# EIB_1xA79026-001_small_pins_v1_2_0_30mm.net
KiCad netlist of a schematic drawn in EAGLE
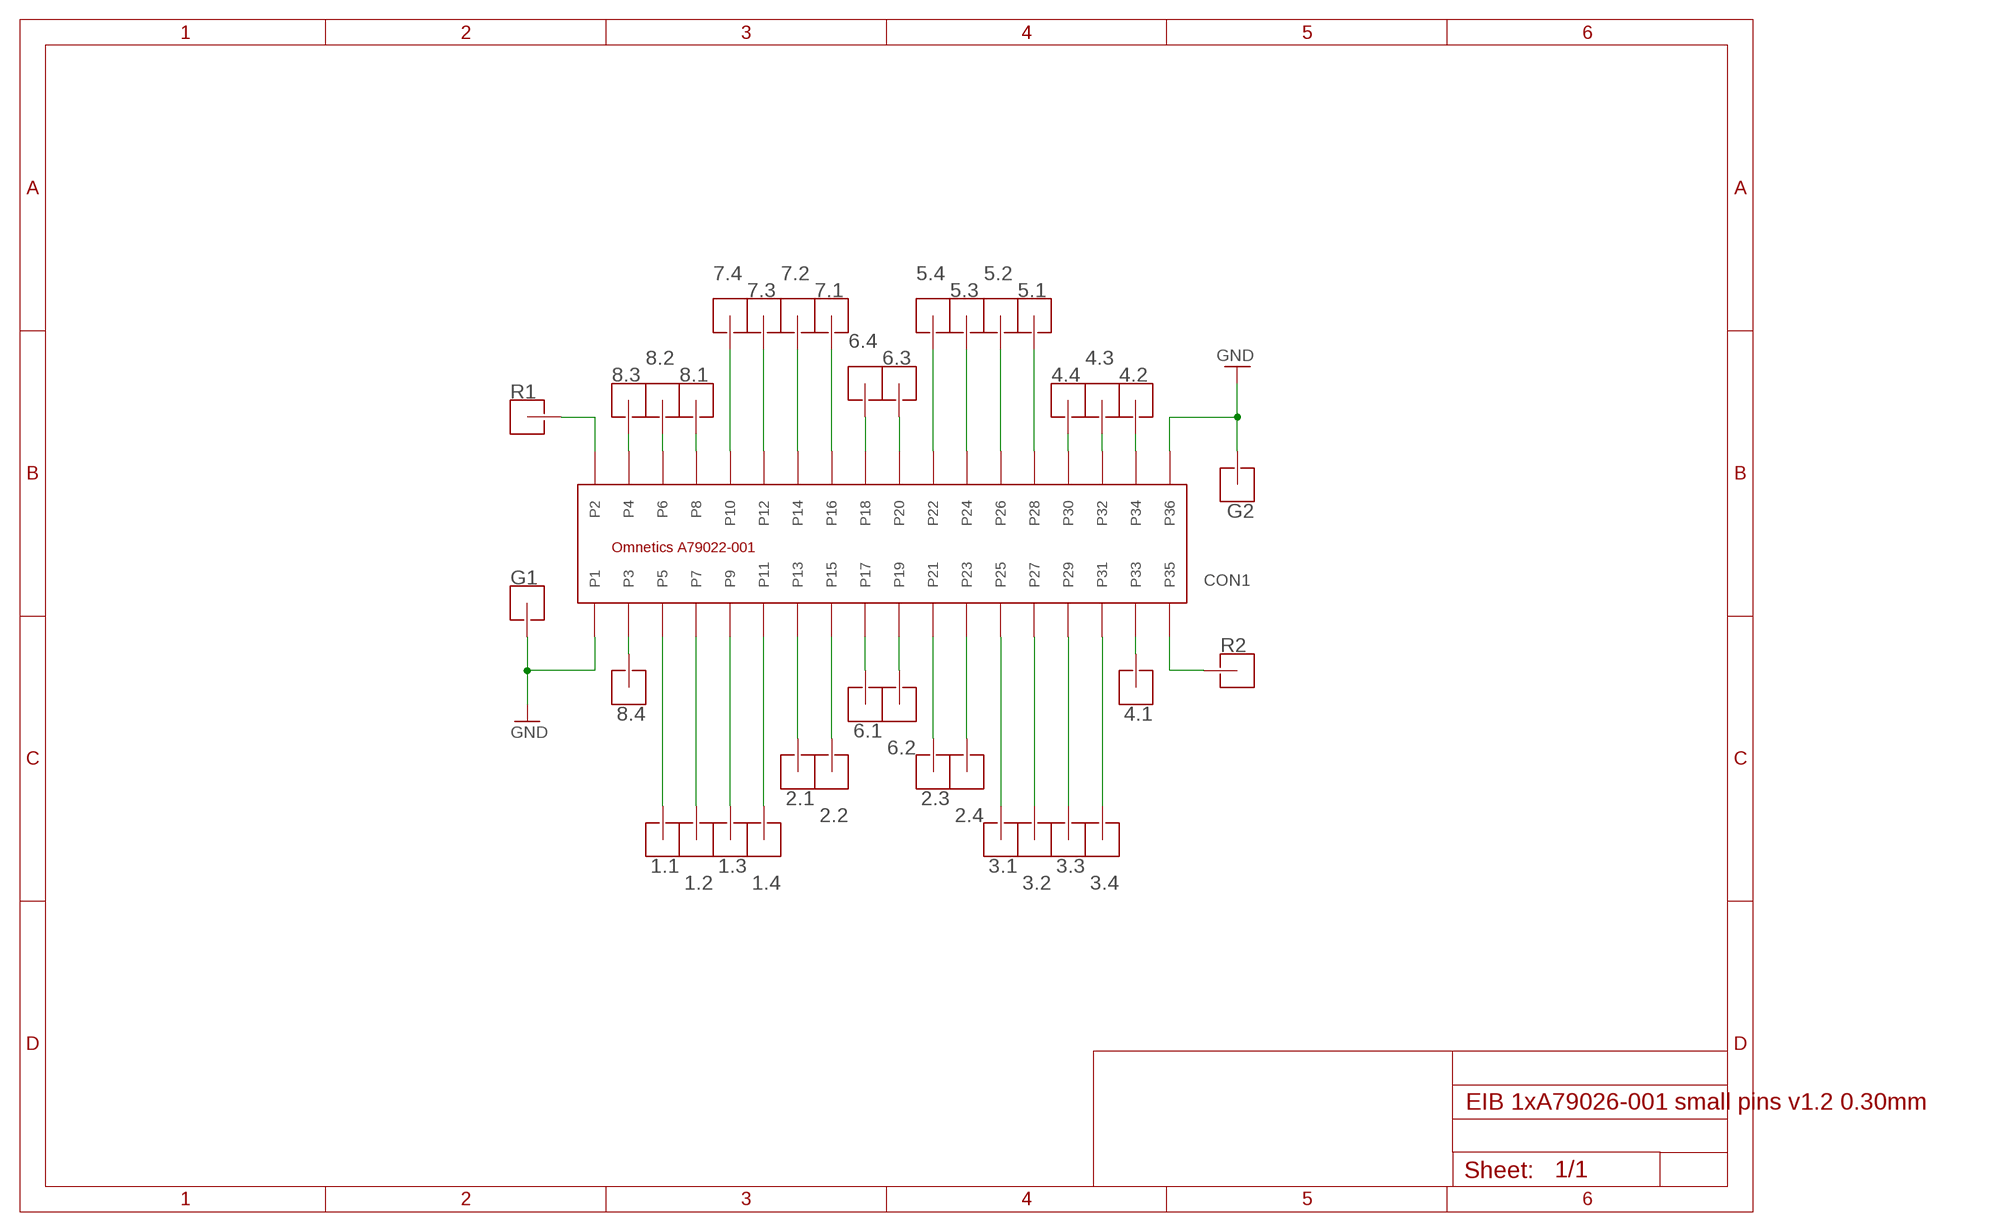
[diagram p0: schematic, sheet 1]

(export (version "E")
  (design (tool "Eeschema 10.0.6"))
  (components
    (comp (ref "1.1")
      (value "HOLE_S_G_PIN_V3")
      (footprint "eagle-import:SMALL_GOLD_PIN_V3")
      (libsource (lib "eagle-import") (part "HOLE_S_G_PIN_V3"))
    )
    (comp (ref "1.2")
      (value "HOLE_S_G_PIN_V3")
      (footprint "eagle-import:SMALL_GOLD_PIN_V3")
      (libsource (lib "eagle-import") (part "HOLE_S_G_PIN_V3"))
    )
    (comp (ref "1.3")
      (value "HOLE_S_G_PIN_V3")
      (footprint "eagle-import:SMALL_GOLD_PIN_V3")
      (libsource (lib "eagle-import") (part "HOLE_S_G_PIN_V3"))
    )
    (comp (ref "1.4")
      (value "HOLE_S_G_PIN_V3")
      (footprint "eagle-import:SMALL_GOLD_PIN_V3")
      (libsource (lib "eagle-import") (part "HOLE_S_G_PIN_V3"))
    )
    (comp (ref "2.1")
      (value "HOLE_S_G_PIN_V3")
      (footprint "eagle-import:SMALL_GOLD_PIN_V3")
      (libsource (lib "eagle-import") (part "HOLE_S_G_PIN_V3"))
    )
    (comp (ref "2.2")
      (value "HOLE_S_G_PIN_V3")
      (footprint "eagle-import:SMALL_GOLD_PIN_V3")
      (libsource (lib "eagle-import") (part "HOLE_S_G_PIN_V3"))
    )
    (comp (ref "2.3")
      (value "HOLE_S_G_PIN_V3")
      (footprint "eagle-import:SMALL_GOLD_PIN_V3")
      (libsource (lib "eagle-import") (part "HOLE_S_G_PIN_V3"))
    )
    (comp (ref "2.4")
      (value "HOLE_S_G_PIN_V3")
      (footprint "eagle-import:SMALL_GOLD_PIN_V3")
      (libsource (lib "eagle-import") (part "HOLE_S_G_PIN_V3"))
    )
    (comp (ref "3.1")
      (value "HOLE_S_G_PIN_V3")
      (footprint "eagle-import:SMALL_GOLD_PIN_V3")
      (libsource (lib "eagle-import") (part "HOLE_S_G_PIN_V3"))
    )
    (comp (ref "3.2")
      (value "HOLE_S_G_PIN_V3")
      (footprint "eagle-import:SMALL_GOLD_PIN_V3")
      (libsource (lib "eagle-import") (part "HOLE_S_G_PIN_V3"))
    )
    (comp (ref "3.3")
      (value "HOLE_S_G_PIN_V3")
      (footprint "eagle-import:SMALL_GOLD_PIN_V3")
      (libsource (lib "eagle-import") (part "HOLE_S_G_PIN_V3"))
    )
    (comp (ref "3.4")
      (value "HOLE_S_G_PIN_V3")
      (footprint "eagle-import:SMALL_GOLD_PIN_V3")
      (libsource (lib "eagle-import") (part "HOLE_S_G_PIN_V3"))
    )
    (comp (ref "4.1")
      (value "HOLE_S_G_PIN_V3")
      (footprint "eagle-import:SMALL_GOLD_PIN_V3")
      (libsource (lib "eagle-import") (part "HOLE_S_G_PIN_V3"))
    )
    (comp (ref "4.2")
      (value "HOLE_S_G_PIN_V3")
      (footprint "eagle-import:SMALL_GOLD_PIN_V3")
      (libsource (lib "eagle-import") (part "HOLE_S_G_PIN_V3"))
    )
    (comp (ref "4.3")
      (value "HOLE_S_G_PIN_V3")
      (footprint "eagle-import:SMALL_GOLD_PIN_V3")
      (libsource (lib "eagle-import") (part "HOLE_S_G_PIN_V3"))
    )
    (comp (ref "4.4")
      (value "HOLE_S_G_PIN_V3")
      (footprint "eagle-import:SMALL_GOLD_PIN_V3")
      (libsource (lib "eagle-import") (part "HOLE_S_G_PIN_V3"))
    )
    (comp (ref "5.1")
      (value "HOLE_S_G_PIN_V3")
      (footprint "eagle-import:SMALL_GOLD_PIN_V3")
      (libsource (lib "eagle-import") (part "HOLE_S_G_PIN_V3"))
    )
    (comp (ref "5.2")
      (value "HOLE_S_G_PIN_V3")
      (footprint "eagle-import:SMALL_GOLD_PIN_V3")
      (libsource (lib "eagle-import") (part "HOLE_S_G_PIN_V3"))
    )
    (comp (ref "5.3")
      (value "HOLE_S_G_PIN_V3")
      (footprint "eagle-import:SMALL_GOLD_PIN_V3")
      (libsource (lib "eagle-import") (part "HOLE_S_G_PIN_V3"))
    )
    (comp (ref "5.4")
      (value "HOLE_S_G_PIN_V3")
      (footprint "eagle-import:SMALL_GOLD_PIN_V3")
      (libsource (lib "eagle-import") (part "HOLE_S_G_PIN_V3"))
    )
    (comp (ref "6.1")
      (value "HOLE_S_G_PIN_V3")
      (footprint "eagle-import:SMALL_GOLD_PIN_V3")
      (libsource (lib "eagle-import") (part "HOLE_S_G_PIN_V3"))
    )
    (comp (ref "6.2")
      (value "HOLE_S_G_PIN_V3")
      (footprint "eagle-import:SMALL_GOLD_PIN_V3")
      (libsource (lib "eagle-import") (part "HOLE_S_G_PIN_V3"))
    )
    (comp (ref "6.3")
      (value "HOLE_S_G_PIN_V3")
      (footprint "eagle-import:SMALL_GOLD_PIN_V3")
      (libsource (lib "eagle-import") (part "HOLE_S_G_PIN_V3"))
    )
    (comp (ref "6.4")
      (value "HOLE_S_G_PIN_V3")
      (footprint "eagle-import:SMALL_GOLD_PIN_V3")
      (libsource (lib "eagle-import") (part "HOLE_S_G_PIN_V3"))
    )
    (comp (ref "7.1")
      (value "HOLE_S_G_PIN_V3")
      (footprint "eagle-import:SMALL_GOLD_PIN_V3")
      (libsource (lib "eagle-import") (part "HOLE_S_G_PIN_V3"))
    )
    (comp (ref "7.2")
      (value "HOLE_S_G_PIN_V3")
      (footprint "eagle-import:SMALL_GOLD_PIN_V3")
      (libsource (lib "eagle-import") (part "HOLE_S_G_PIN_V3"))
    )
    (comp (ref "7.3")
      (value "HOLE_S_G_PIN_V3")
      (footprint "eagle-import:SMALL_GOLD_PIN_V3")
      (libsource (lib "eagle-import") (part "HOLE_S_G_PIN_V3"))
    )
    (comp (ref "7.4")
      (value "HOLE_S_G_PIN_V3")
      (footprint "eagle-import:SMALL_GOLD_PIN_V3")
      (libsource (lib "eagle-import") (part "HOLE_S_G_PIN_V3"))
    )
    (comp (ref "8.1")
      (value "HOLE_S_G_PIN_V3")
      (footprint "eagle-import:SMALL_GOLD_PIN_V3")
      (libsource (lib "eagle-import") (part "HOLE_S_G_PIN_V3"))
    )
    (comp (ref "8.2")
      (value "HOLE_S_G_PIN_V3")
      (footprint "eagle-import:SMALL_GOLD_PIN_V3")
      (libsource (lib "eagle-import") (part "HOLE_S_G_PIN_V3"))
    )
    (comp (ref "8.3")
      (value "HOLE_S_G_PIN_V3")
      (footprint "eagle-import:SMALL_GOLD_PIN_V3")
      (libsource (lib "eagle-import") (part "HOLE_S_G_PIN_V3"))
    )
    (comp (ref "8.4")
      (value "HOLE_S_G_PIN_V3")
      (footprint "eagle-import:SMALL_GOLD_PIN_V3")
      (libsource (lib "eagle-import") (part "HOLE_S_G_PIN_V3"))
    )
    (comp (ref "CON1")
      (value "A79022-001_MALESMD")
      (footprint "eagle-import:A79026-001_MALE")
      (libsource (lib "eagle-import") (part "A79022-001_MALESMD"))
    )
    (comp (ref "G1")
      (value "HOLE_S_G_PIN_V3")
      (footprint "eagle-import:SMALL_GOLD_PIN_V3")
      (libsource (lib "eagle-import") (part "HOLE_S_G_PIN_V3"))
    )
    (comp (ref "G2")
      (value "HOLE_S_G_PIN_V3")
      (footprint "eagle-import:SMALL_GOLD_PIN_V3")
      (libsource (lib "eagle-import") (part "HOLE_S_G_PIN_V3"))
    )
    (comp (ref "R1")
      (value "HOLE_S_G_PIN_V3")
      (footprint "eagle-import:SMALL_GOLD_PIN_V3")
      (libsource (lib "eagle-import") (part "HOLE_S_G_PIN_V3"))
    )
    (comp (ref "R2")
      (value "HOLE_S_G_PIN_V3")
      (footprint "eagle-import:SMALL_GOLD_PIN_V3")
      (libsource (lib "eagle-import") (part "HOLE_S_G_PIN_V3"))
    )
  )
  (nets
    (net (code "1") (name "GND") (class "Default")
      (node (ref "CON1") (pin "P1") (pinfunction "P1_P1") (pintype "bidirectional"))
      (node (ref "CON1") (pin "P36") (pinfunction "P36_P36") (pintype "bidirectional"))
      (node (ref "G1") (pin "P$1") (pinfunction "P$1_P$1") (pintype "bidirectional"))
      (node (ref "G2") (pin "P$1") (pinfunction "P$1_P$1") (pintype "bidirectional"))
    )
    (net (code "2") (name "Net-(1.1-PadP$1)") (class "Default")
      (node (ref "1.1") (pin "P$1") (pinfunction "P$1_P$1") (pintype "bidirectional"))
      (node (ref "CON1") (pin "P5") (pinfunction "P5_P5") (pintype "bidirectional"))
    )
    (net (code "3") (name "Net-(1.2-PadP$1)") (class "Default")
      (node (ref "1.2") (pin "P$1") (pinfunction "P$1_P$1") (pintype "bidirectional"))
      (node (ref "CON1") (pin "P7") (pinfunction "P7_P7") (pintype "bidirectional"))
    )
    (net (code "4") (name "Net-(1.3-PadP$1)") (class "Default")
      (node (ref "1.3") (pin "P$1") (pinfunction "P$1_P$1") (pintype "bidirectional"))
      (node (ref "CON1") (pin "P9") (pinfunction "P9_P9") (pintype "bidirectional"))
    )
    (net (code "5") (name "Net-(1.4-PadP$1)") (class "Default")
      (node (ref "1.4") (pin "P$1") (pinfunction "P$1_P$1") (pintype "bidirectional"))
      (node (ref "CON1") (pin "P11") (pinfunction "P11_P11") (pintype "bidirectional"))
    )
    (net (code "6") (name "Net-(2.1-PadP$1)") (class "Default")
      (node (ref "2.1") (pin "P$1") (pinfunction "P$1_P$1") (pintype "bidirectional"))
      (node (ref "CON1") (pin "P13") (pinfunction "P13_P13") (pintype "bidirectional"))
    )
    (net (code "7") (name "Net-(2.2-PadP$1)") (class "Default")
      (node (ref "2.2") (pin "P$1") (pinfunction "P$1_P$1") (pintype "bidirectional"))
      (node (ref "CON1") (pin "P15") (pinfunction "P15_P15") (pintype "bidirectional"))
    )
    (net (code "8") (name "Net-(2.3-PadP$1)") (class "Default")
      (node (ref "2.3") (pin "P$1") (pinfunction "P$1_P$1") (pintype "bidirectional"))
      (node (ref "CON1") (pin "P21") (pinfunction "P21_P21") (pintype "bidirectional"))
    )
    (net (code "9") (name "Net-(2.4-PadP$1)") (class "Default")
      (node (ref "2.4") (pin "P$1") (pinfunction "P$1_P$1") (pintype "bidirectional"))
      (node (ref "CON1") (pin "P23") (pinfunction "P23_P23") (pintype "bidirectional"))
    )
    (net (code "10") (name "Net-(3.1-PadP$1)") (class "Default")
      (node (ref "3.1") (pin "P$1") (pinfunction "P$1_P$1") (pintype "bidirectional"))
      (node (ref "CON1") (pin "P25") (pinfunction "P25_P25") (pintype "bidirectional"))
    )
    (net (code "11") (name "Net-(3.2-PadP$1)") (class "Default")
      (node (ref "3.2") (pin "P$1") (pinfunction "P$1_P$1") (pintype "bidirectional"))
      (node (ref "CON1") (pin "P27") (pinfunction "P27_P27") (pintype "bidirectional"))
    )
    (net (code "12") (name "Net-(3.3-PadP$1)") (class "Default")
      (node (ref "3.3") (pin "P$1") (pinfunction "P$1_P$1") (pintype "bidirectional"))
      (node (ref "CON1") (pin "P29") (pinfunction "P29_P29") (pintype "bidirectional"))
    )
    (net (code "13") (name "Net-(3.4-PadP$1)") (class "Default")
      (node (ref "3.4") (pin "P$1") (pinfunction "P$1_P$1") (pintype "bidirectional"))
      (node (ref "CON1") (pin "P31") (pinfunction "P31_P31") (pintype "bidirectional"))
    )
    (net (code "14") (name "Net-(4.1-PadP$1)") (class "Default")
      (node (ref "4.1") (pin "P$1") (pinfunction "P$1_P$1") (pintype "bidirectional"))
      (node (ref "CON1") (pin "P33") (pinfunction "P33_P33") (pintype "bidirectional"))
    )
    (net (code "15") (name "Net-(4.2-PadP$1)") (class "Default")
      (node (ref "4.2") (pin "P$1") (pinfunction "P$1_P$1") (pintype "bidirectional"))
      (node (ref "CON1") (pin "P34") (pinfunction "P34_P34") (pintype "bidirectional"))
    )
    (net (code "16") (name "Net-(4.3-PadP$1)") (class "Default")
      (node (ref "4.3") (pin "P$1") (pinfunction "P$1_P$1") (pintype "bidirectional"))
      (node (ref "CON1") (pin "P32") (pinfunction "P32_P32") (pintype "bidirectional"))
    )
    (net (code "17") (name "Net-(4.4-PadP$1)") (class "Default")
      (node (ref "4.4") (pin "P$1") (pinfunction "P$1_P$1") (pintype "bidirectional"))
      (node (ref "CON1") (pin "P30") (pinfunction "P30_P30") (pintype "bidirectional"))
    )
    (net (code "18") (name "Net-(5.1-PadP$1)") (class "Default")
      (node (ref "5.1") (pin "P$1") (pinfunction "P$1_P$1") (pintype "bidirectional"))
      (node (ref "CON1") (pin "P28") (pinfunction "P28_P28") (pintype "bidirectional"))
    )
    (net (code "19") (name "Net-(5.2-PadP$1)") (class "Default")
      (node (ref "5.2") (pin "P$1") (pinfunction "P$1_P$1") (pintype "bidirectional"))
      (node (ref "CON1") (pin "P26") (pinfunction "P26_P26") (pintype "bidirectional"))
    )
    (net (code "20") (name "Net-(5.3-PadP$1)") (class "Default")
      (node (ref "5.3") (pin "P$1") (pinfunction "P$1_P$1") (pintype "bidirectional"))
      (node (ref "CON1") (pin "P24") (pinfunction "P24_P24") (pintype "bidirectional"))
    )
    (net (code "21") (name "Net-(5.4-PadP$1)") (class "Default")
      (node (ref "5.4") (pin "P$1") (pinfunction "P$1_P$1") (pintype "bidirectional"))
      (node (ref "CON1") (pin "P22") (pinfunction "P22_P22") (pintype "bidirectional"))
    )
    (net (code "22") (name "Net-(6.1-PadP$1)") (class "Default")
      (node (ref "6.1") (pin "P$1") (pinfunction "P$1_P$1") (pintype "bidirectional"))
      (node (ref "CON1") (pin "P17") (pinfunction "P17_P17") (pintype "bidirectional"))
    )
    (net (code "23") (name "Net-(6.2-PadP$1)") (class "Default")
      (node (ref "6.2") (pin "P$1") (pinfunction "P$1_P$1") (pintype "bidirectional"))
      (node (ref "CON1") (pin "P19") (pinfunction "P19_P19") (pintype "bidirectional"))
    )
    (net (code "24") (name "Net-(6.3-PadP$1)") (class "Default")
      (node (ref "6.3") (pin "P$1") (pinfunction "P$1_P$1") (pintype "bidirectional"))
      (node (ref "CON1") (pin "P20") (pinfunction "P20_P20") (pintype "bidirectional"))
    )
    (net (code "25") (name "Net-(6.4-PadP$1)") (class "Default")
      (node (ref "6.4") (pin "P$1") (pinfunction "P$1_P$1") (pintype "bidirectional"))
      (node (ref "CON1") (pin "P18") (pinfunction "P18_P18") (pintype "bidirectional"))
    )
    (net (code "26") (name "Net-(7.1-PadP$1)") (class "Default")
      (node (ref "7.1") (pin "P$1") (pinfunction "P$1_P$1") (pintype "bidirectional"))
      (node (ref "CON1") (pin "P16") (pinfunction "P16_P16") (pintype "bidirectional"))
    )
    (net (code "27") (name "Net-(7.2-PadP$1)") (class "Default")
      (node (ref "7.2") (pin "P$1") (pinfunction "P$1_P$1") (pintype "bidirectional"))
      (node (ref "CON1") (pin "P14") (pinfunction "P14_P14") (pintype "bidirectional"))
    )
    (net (code "28") (name "Net-(7.3-PadP$1)") (class "Default")
      (node (ref "7.3") (pin "P$1") (pinfunction "P$1_P$1") (pintype "bidirectional"))
      (node (ref "CON1") (pin "P12") (pinfunction "P12_P12") (pintype "bidirectional"))
    )
    (net (code "29") (name "Net-(7.4-PadP$1)") (class "Default")
      (node (ref "7.4") (pin "P$1") (pinfunction "P$1_P$1") (pintype "bidirectional"))
      (node (ref "CON1") (pin "P10") (pinfunction "P10_P10") (pintype "bidirectional"))
    )
    (net (code "30") (name "Net-(8.1-PadP$1)") (class "Default")
      (node (ref "8.1") (pin "P$1") (pinfunction "P$1_P$1") (pintype "bidirectional"))
      (node (ref "CON1") (pin "P8") (pinfunction "P8_P8") (pintype "bidirectional"))
    )
    (net (code "31") (name "Net-(8.2-PadP$1)") (class "Default")
      (node (ref "8.2") (pin "P$1") (pinfunction "P$1_P$1") (pintype "bidirectional"))
      (node (ref "CON1") (pin "P6") (pinfunction "P6_P6") (pintype "bidirectional"))
    )
    (net (code "32") (name "Net-(8.3-PadP$1)") (class "Default")
      (node (ref "8.3") (pin "P$1") (pinfunction "P$1_P$1") (pintype "bidirectional"))
      (node (ref "CON1") (pin "P4") (pinfunction "P4_P4") (pintype "bidirectional"))
    )
    (net (code "33") (name "Net-(8.4-PadP$1)") (class "Default")
      (node (ref "8.4") (pin "P$1") (pinfunction "P$1_P$1") (pintype "bidirectional"))
      (node (ref "CON1") (pin "P3") (pinfunction "P3_P3") (pintype "bidirectional"))
    )
    (net (code "34") (name "Net-(CON1-PadP2)") (class "Default")
      (node (ref "CON1") (pin "P2") (pinfunction "P2_P2") (pintype "bidirectional"))
      (node (ref "R1") (pin "P$1") (pinfunction "P$1_P$1") (pintype "bidirectional"))
    )
    (net (code "35") (name "Net-(CON1-PadP35)") (class "Default")
      (node (ref "CON1") (pin "P35") (pinfunction "P35_P35") (pintype "bidirectional"))
      (node (ref "R2") (pin "P$1") (pinfunction "P$1_P$1") (pintype "bidirectional"))
    )
  )
)
